# power.net
KiCad netlist of a schematic drawn in Altium Designer
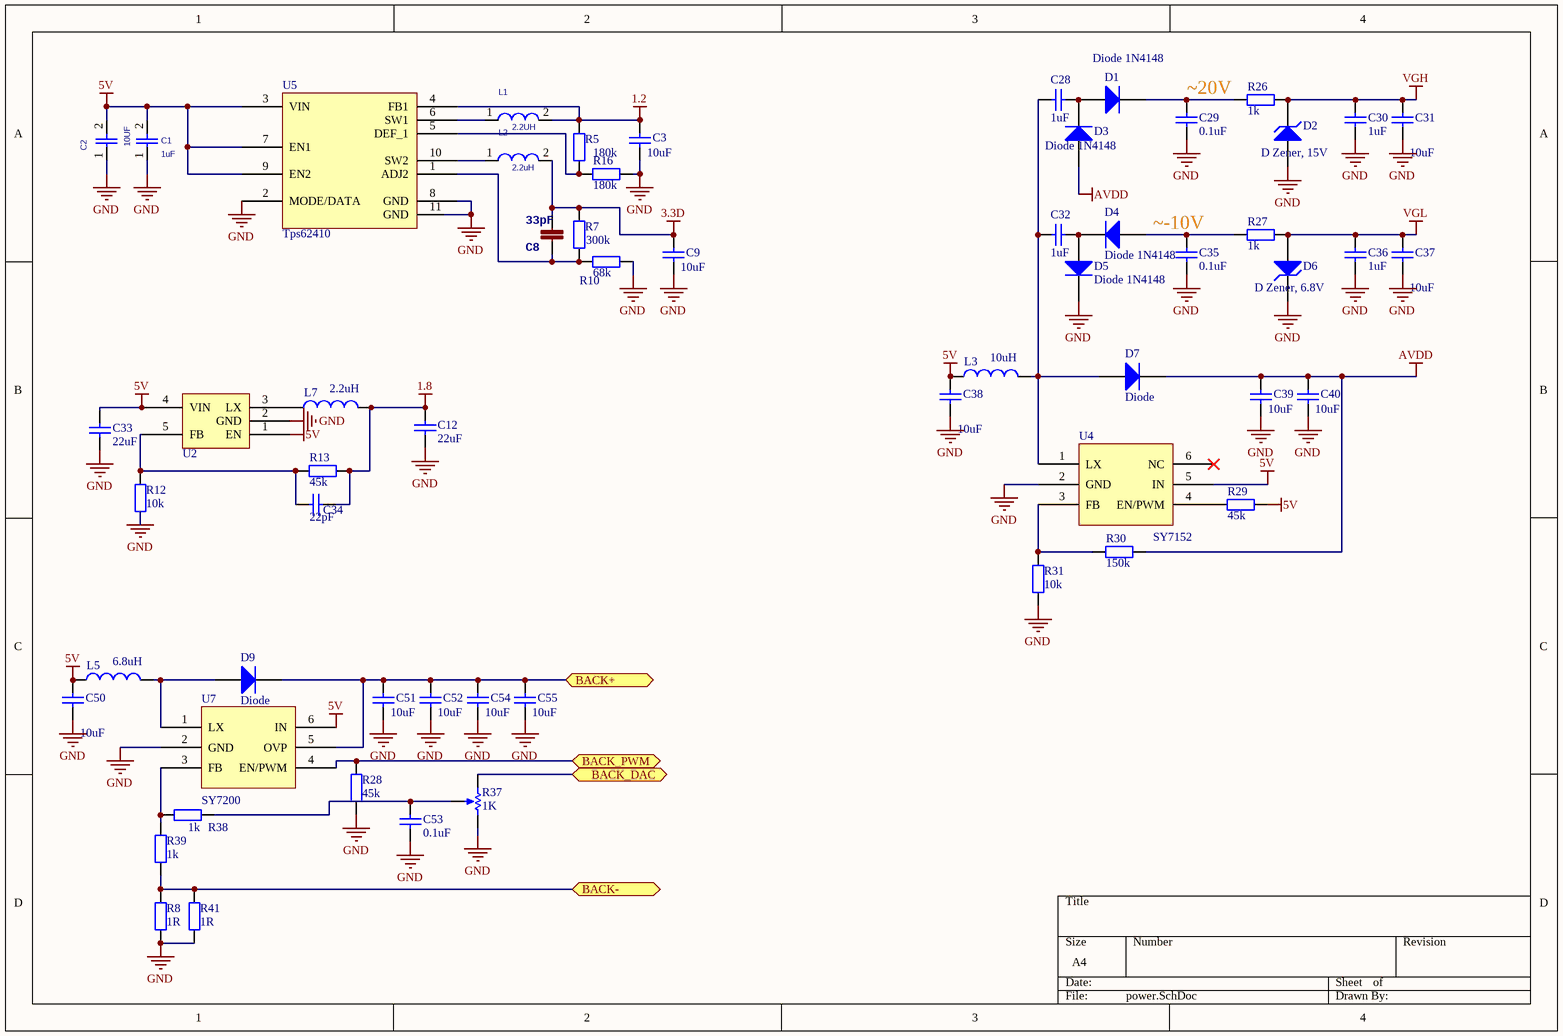
[diagram p0: power.SchDoc]

(export (version "E")
  (design (tool "Eeschema 10.0.6"))
  (components
    (comp (ref "C1") (value "1uF") (footprint "0603") (libsource (lib "*") (part "CAP/0402")))
    (comp (ref "C2") (value "10UF") (footprint "0805") (libsource (lib "*") (part "CAP/0402")))
    (comp (ref "C3")
      (value "10uF")
      (footprint "0805")
      (description "Capacitor")
      (fields (field (name "PUBLISHER") "Altium Limited"))
      (libsource (lib "RTC6705") (part "Cap"))
    )
    (comp (ref "C8")
      (value "33pF")
      (footprint "0402")
      (description "<b>Capacitor</b>\nStandard 0603 ceramic capacitor, and 0.1\" leaded capacitor.")
      (fields (field (name "PARTNO") "CC0402ZRY5V7BB104"))
      (libsource (lib "*") (part "CAP0402-CAP"))
    )
    (comp (ref "C9")
      (value "10uF")
      (footprint "0805")
      (description "Capacitor")
      (fields (field (name "PUBLISHER") "Altium Limited"))
      (libsource (lib "RTC6705") (part "Cap"))
    )
    (comp (ref "C12")
      (value "22uF")
      (footprint "0805")
      (description "Capacitor")
      (fields (field (name "Comment") "Cap") (field (name "PUBLISHER") "Altium Limited"))
      (libsource (lib "RTC6705") (part "Cap"))
    )
    (comp (ref "C28")
      (value "1uF")
      (footprint "0603")
      (description "Capacitor")
      (fields (field (name "PUBLISHER") "Altium Limited"))
      (libsource (lib "RTC6705") (part "Cap"))
    )
    (comp (ref "C29")
      (value "0.1uF")
      (footprint "0603")
      (description "Capacitor")
      (fields (field (name "PUBLISHER") "Altium Limited"))
      (libsource (lib "RTC6705") (part "Cap"))
    )
    (comp (ref "C30")
      (value "1uF")
      (footprint "0603")
      (description "Capacitor")
      (fields (field (name "PUBLISHER") "Altium Limited"))
      (libsource (lib "RTC6705") (part "Cap"))
    )
    (comp (ref "C31")
      (value "10uF")
      (footprint "0805")
      (description "Capacitor")
      (fields (field (name "PUBLISHER") "Altium Limited"))
      (libsource (lib "RTC6705") (part "Cap"))
    )
    (comp (ref "C32")
      (value "1uF")
      (footprint "0603")
      (description "Capacitor")
      (fields (field (name "PUBLISHER") "Altium Limited"))
      (libsource (lib "RTC6705") (part "Cap"))
    )
    (comp (ref "C33")
      (value "22uF")
      (footprint "0805")
      (description "Capacitor")
      (fields (field (name "Comment") "Cap") (field (name "PUBLISHER") "Altium Limited"))
      (libsource (lib "RTC6705") (part "Cap"))
    )
    (comp (ref "C34")
      (value "22pF")
      (footprint "0402")
      (description "Capacitor")
      (fields (field (name "PUBLISHER") "Altium Limited"))
      (libsource (lib "RTC6705") (part "Cap"))
    )
    (comp (ref "C35")
      (value "0.1uF")
      (footprint "0603")
      (description "Capacitor")
      (fields (field (name "PUBLISHER") "Altium Limited"))
      (libsource (lib "RTC6705") (part "Cap"))
    )
    (comp (ref "C36")
      (value "1uF")
      (footprint "0603")
      (description "Capacitor")
      (fields (field (name "PUBLISHER") "Altium Limited"))
      (libsource (lib "RTC6705") (part "Cap"))
    )
    (comp (ref "C37")
      (value "10uF")
      (footprint "0805")
      (description "Capacitor")
      (fields (field (name "PUBLISHER") "Altium Limited"))
      (libsource (lib "RTC6705") (part "Cap"))
    )
    (comp (ref "C38")
      (value "10uF")
      (footprint "0805")
      (description "Capacitor")
      (fields (field (name "PUBLISHER") "Altium Limited"))
      (libsource (lib "RTC6705") (part "Cap"))
    )
    (comp (ref "C39")
      (value "10uF")
      (footprint "0805")
      (description "Capacitor")
      (fields (field (name "PUBLISHER") "Altium Limited"))
      (libsource (lib "RTC6705") (part "Cap"))
    )
    (comp (ref "C40")
      (value "10uF")
      (footprint "0805")
      (description "Capacitor")
      (fields (field (name "PUBLISHER") "Altium Limited"))
      (libsource (lib "RTC6705") (part "Cap"))
    )
    (comp (ref "C50")
      (value "10uF")
      (footprint "0805")
      (description "Capacitor")
      (fields (field (name "PUBLISHER") "Altium Limited"))
      (libsource (lib "RTC6705") (part "Cap"))
    )
    (comp (ref "C51")
      (value "10uF")
      (footprint "0805")
      (description "Capacitor")
      (fields (field (name "PUBLISHER") "Altium Limited"))
      (libsource (lib "RTC6705") (part "Cap"))
    )
    (comp (ref "C52")
      (value "10uF")
      (footprint "0805")
      (description "Capacitor")
      (fields (field (name "PUBLISHER") "Altium Limited"))
      (libsource (lib "RTC6705") (part "Cap"))
    )
    (comp (ref "C53")
      (value "0.1uF")
      (footprint "0402")
      (description "Capacitor")
      (fields (field (name "PUBLISHER") "Altium Limited"))
      (libsource (lib "RTC6705") (part "Cap"))
    )
    (comp (ref "C54")
      (value "10uF")
      (footprint "0603")
      (description "Capacitor")
      (fields (field (name "PUBLISHER") "Altium Limited"))
      (libsource (lib "RTC6705") (part "Cap"))
    )
    (comp (ref "C55")
      (value "10uF")
      (footprint "0603")
      (description "Capacitor")
      (fields (field (name "PUBLISHER") "Altium Limited"))
      (libsource (lib "RTC6705") (part "Cap"))
    )
    (comp (ref "D1")
      (value "Diode 1N4148")
      (footprint "LC-SOD-323")
      (description "High Conductance Fast Diode")
      (fields (field (name "PUBLISHER") "Altium Limited"))
      (libsource (lib "Miscellaneous Devices") (part "Diode 1N4148"))
    )
    (comp (ref "D2")
      (value "D Zener, 15V")
      (footprint "LC-SOD-323")
      (description "Zener Diode")
      (fields (field (name "PUBLISHER") "Altium Limited"))
      (libsource (lib "Miscellaneous Devices") (part "D Zener"))
    )
    (comp (ref "D3")
      (value "Diode 1N4148")
      (footprint "LC-SOD-323")
      (description "High Conductance Fast Diode")
      (fields (field (name "PUBLISHER") "Altium Limited"))
      (libsource (lib "Miscellaneous Devices") (part "Diode 1N4148"))
    )
    (comp (ref "D4")
      (value "Diode 1N4148")
      (footprint "LC-SOD-323")
      (description "High Conductance Fast Diode")
      (fields (field (name "PUBLISHER") "Altium Limited"))
      (libsource (lib "Miscellaneous Devices") (part "Diode 1N4148"))
    )
    (comp (ref "D5")
      (value "Diode 1N4148")
      (footprint "LC-SOD-323")
      (description "High Conductance Fast Diode")
      (fields (field (name "PUBLISHER") "Altium Limited"))
      (libsource (lib "Miscellaneous Devices") (part "Diode 1N4148"))
    )
    (comp (ref "D6")
      (value "D Zener, 6.8V")
      (footprint "LC-SOD-323")
      (description "Zener Diode")
      (fields (field (name "PUBLISHER") "Altium Limited"))
      (libsource (lib "Miscellaneous Devices") (part "D Zener"))
    )
    (comp (ref "D7")
      (value "Diode")
      (footprint "LC-SOD-323")
      (description "Default Diode")
      (fields (field (name "PUBLISHER") "Altium Limited"))
      (libsource (lib "Miscellaneous Devices") (part "Diode"))
    )
    (comp (ref "D9")
      (value "Diode")
      (footprint "SMA")
      (description "Default Diode")
      (fields (field (name "PUBLISHER") "Altium Limited"))
      (libsource (lib "Miscellaneous Devices") (part "Diode"))
    )
    (comp (ref "L1") (value "2.2UH") (footprint "0806") (libsource (lib "*") (part "L/2.5*2.0")))
    (comp (ref "L2") (value "2.2uH") (footprint "0806") (libsource (lib "*") (part "L/2.5*2.0")))
    (comp (ref "L3")
      (value "10uH")
      (footprint "0806")
      (description "Inductor")
      (fields (field (name "PUBLISHER") "Altium Limited"))
      (libsource (lib "Miscellaneous Devices") (part "Inductor"))
    )
    (comp (ref "L5")
      (value "6.8uH")
      (footprint "L4015")
      (description "Inductor")
      (fields (field (name "PUBLISHER") "Altium Limited"))
      (libsource (lib "Miscellaneous Devices") (part "Inductor"))
    )
    (comp (ref "L7")
      (value "2.2uH")
      (footprint "0806")
      (description "Inductor")
      (fields (field (name "PUBLISHER") "Altium Limited"))
      (libsource (lib "Miscellaneous Devices") (part "Inductor"))
    )
    (comp (ref "R5")
      (value "180k")
      (footprint "0402")
      (description "Resistor")
      (fields (field (name "PUBLISHER") "Altium Limited"))
      (libsource (lib "") (part "Res2_2"))
    )
    (comp (ref "R7")
      (value "300k")
      (footprint "0402")
      (description "Resistor")
      (fields (field (name "PUBLISHER") "Altium Limited"))
      (libsource (lib "") (part "Res2_2"))
    )
    (comp (ref "R8")
      (value "1R")
      (footprint "0805")
      (description "Resistor")
      (fields (field (name "PUBLISHER") "Altium Limited"))
      (libsource (lib "RTC6705") (part "Res2"))
    )
    (comp (ref "R10")
      (value "68k")
      (footprint "0402")
      (description "Resistor")
      (fields (field (name "PUBLISHER") "Altium Limited"))
      (libsource (lib "") (part "Res2_1"))
    )
    (comp (ref "R12")
      (value "10k")
      (footprint "0402")
      (description "Resistor")
      (fields (field (name "PUBLISHER") "Altium Limited"))
      (libsource (lib "RTC6705") (part "Res2"))
    )
    (comp (ref "R13")
      (value "45k")
      (footprint "0402")
      (description "Resistor")
      (fields (field (name "PUBLISHER") "Altium Limited"))
      (libsource (lib "") (part "Res2_1"))
    )
    (comp (ref "R16")
      (value "180k")
      (footprint "0402")
      (description "Resistor")
      (fields (field (name "PUBLISHER") "Altium Limited"))
      (libsource (lib "") (part "Res2_1"))
    )
    (comp (ref "R26")
      (value "1k")
      (footprint "0402")
      (description "Resistor")
      (fields (field (name "PUBLISHER") "Altium Limited"))
      (libsource (lib "") (part "Res2_1"))
    )
    (comp (ref "R27")
      (value "1k")
      (footprint "0402")
      (description "Resistor")
      (fields (field (name "PUBLISHER") "Altium Limited"))
      (libsource (lib "") (part "Res2_1"))
    )
    (comp (ref "R28")
      (value "45k")
      (footprint "0402")
      (description "Resistor")
      (fields (field (name "PUBLISHER") "Altium Limited"))
      (libsource (lib "RTC6705") (part "Res2"))
    )
    (comp (ref "R29")
      (value "45k")
      (footprint "0402")
      (description "Resistor")
      (fields (field (name "PUBLISHER") "Altium Limited"))
      (libsource (lib "") (part "Res2_1"))
    )
    (comp (ref "R30")
      (value "150k")
      (footprint "0402")
      (description "Resistor")
      (fields (field (name "PUBLISHER") "Altium Limited"))
      (libsource (lib "") (part "Res2_1"))
    )
    (comp (ref "R31")
      (value "10k")
      (footprint "0402")
      (description "Resistor")
      (fields (field (name "PUBLISHER") "Altium Limited"))
      (libsource (lib "RTC6705") (part "Res2"))
    )
    (comp (ref "R37")
      (value "1K")
      (footprint "POT1")
      (description "Potentiometer")
      (fields (field (name "Comment") "RPot") (field (name "PUBLISHER") "Altium Limited"))
      (libsource (lib "Miscellaneous Devices") (part "RPot"))
    )
    (comp (ref "R38")
      (value "1k")
      (footprint "0402")
      (description "Resistor")
      (fields (field (name "PUBLISHER") "Altium Limited"))
      (libsource (lib "") (part "Res2_3"))
    )
    (comp (ref "R39")
      (value "1k")
      (footprint "0402")
      (description "Resistor")
      (fields (field (name "PUBLISHER") "Altium Limited"))
      (libsource (lib "RTC6705") (part "Res2"))
    )
    (comp (ref "R41")
      (value "1R")
      (footprint "0805")
      (description "Resistor")
      (fields (field (name "PUBLISHER") "Altium Limited"))
      (libsource (lib "RTC6705") (part "Res2"))
    )
    (comp (ref "U2") (value "RT8059") (footprint "SOT23-5") (libsource (lib "WifiGain") (part "RT8059")))
    (comp (ref "U4") (value "SY7152") (footprint "SOT23-6") (libsource (lib "sch") (part "SY7152")))
    (comp (ref "U5") (value "Tps62410") (footprint "DFN-10P-3X3") (libsource (lib "Euler") (part "Tps62410")))
    (comp (ref "U7") (value "SY7200") (footprint "SOT23-6") (libsource (lib "sch") (part "SY7200")))
  )
  (nets
    (net (code "1") (name "/BACK+") (class "Default")
      (node (ref "C51") (pin "2") (pinfunction "2_2") (pintype "passive"))
      (node (ref "C52") (pin "2") (pinfunction "2_2") (pintype "passive"))
      (node (ref "C54") (pin "2") (pinfunction "2_2") (pintype "passive"))
      (node (ref "C55") (pin "2") (pinfunction "2_2") (pintype "passive"))
      (node (ref "D9") (pin "2") (pinfunction "K_2") (pintype "passive"))
      (node (ref "U7") (pin "5") (pinfunction "OVP_5") (pintype "passive"))
    )
    (net (code "2") (name "/BACK-") (class "Default")
      (node (ref "R39") (pin "1") (pinfunction "1_1") (pintype "passive"))
      (node (ref "R41") (pin "2") (pinfunction "2_2") (pintype "passive"))
      (node (ref "R8") (pin "2") (pinfunction "2_2") (pintype "passive"))
    )
    (net (code "3") (name "/BACK_DAC") (class "Default")
      (node (ref "R37") (pin "1") (pinfunction "TOP_1") (pintype "passive"))
    )
    (net (code "4") (name "/BACK_PWM") (class "Default")
      (node (ref "R28") (pin "2") (pinfunction "2_2") (pintype "passive"))
      (node (ref "U7") (pin "4") (pinfunction "EN/PWM_4") (pintype "passive"))
    )
    (net (code "5") (name "1.2") (class "Default")
      (node (ref "C3") (pin "2") (pinfunction "2_2") (pintype "passive"))
      (node (ref "L1") (pin "2") (pinfunction "2_2") (pintype "passive"))
      (node (ref "R5") (pin "1") (pinfunction "1_1") (pintype "passive"))
      (node (ref "U5") (pin "4") (pinfunction "FB1_4") (pintype "passive"))
    )
    (net (code "6") (name "1.8") (class "Default")
      (node (ref "C12") (pin "2") (pinfunction "2_2") (pintype "passive"))
      (node (ref "C34") (pin "1") (pinfunction "1_1") (pintype "passive"))
      (node (ref "L7") (pin "2") (pinfunction "2_2") (pintype "passive"))
      (node (ref "R13") (pin "2") (pinfunction "2_2") (pintype "passive"))
    )
    (net (code "7") (name "3.3D") (class "Default")
      (node (ref "C8") (pin "1") (pinfunction "1_1") (pintype "passive"))
      (node (ref "C9") (pin "2") (pinfunction "2_2") (pintype "passive"))
      (node (ref "L2") (pin "2") (pinfunction "2_2") (pintype "passive"))
      (node (ref "R7") (pin "1") (pinfunction "1_1") (pintype "passive"))
    )
    (net (code "8") (name "5V") (class "Default")
      (node (ref "C1") (pin "2") (pinfunction "2_2") (pintype "passive"))
      (node (ref "C2") (pin "2") (pinfunction "2_2") (pintype "passive"))
      (node (ref "C33") (pin "2") (pinfunction "2_2") (pintype "passive"))
      (node (ref "C38") (pin "2") (pinfunction "2_2") (pintype "passive"))
      (node (ref "C50") (pin "2") (pinfunction "2_2") (pintype "passive"))
      (node (ref "L3") (pin "1") (pinfunction "1_1") (pintype "passive"))
      (node (ref "L5") (pin "1") (pinfunction "1_1") (pintype "passive"))
      (node (ref "R29") (pin "2") (pinfunction "2_2") (pintype "passive"))
      (node (ref "U2") (pin "1") (pinfunction "EN_1") (pintype "passive"))
      (node (ref "U2") (pin "4") (pinfunction "VIN_4") (pintype "passive"))
      (node (ref "U4") (pin "5") (pinfunction "IN_5") (pintype "passive"))
      (node (ref "U5") (pin "3") (pinfunction "VIN_3") (pintype "passive"))
      (node (ref "U5") (pin "7") (pinfunction "EN1_7") (pintype "passive"))
      (node (ref "U5") (pin "9") (pinfunction "EN2_9") (pintype "passive"))
      (node (ref "U7") (pin "6") (pinfunction "IN_6") (pintype "passive"))
    )
    (net (code "9") (name "AVDD") (class "Default")
      (node (ref "C39") (pin "2") (pinfunction "2_2") (pintype "passive"))
      (node (ref "C40") (pin "2") (pinfunction "2_2") (pintype "passive"))
      (node (ref "D3") (pin "1") (pinfunction "A_1") (pintype "passive"))
      (node (ref "D7") (pin "2") (pinfunction "K_2") (pintype "passive"))
      (node (ref "R30") (pin "2") (pinfunction "2_2") (pintype "passive"))
    )
    (net (code "10") (name "GND") (class "Default")
      (node (ref "C1") (pin "1") (pinfunction "1_1") (pintype "passive"))
      (node (ref "C12") (pin "1") (pinfunction "1_1") (pintype "passive"))
      (node (ref "C2") (pin "1") (pinfunction "1_1") (pintype "passive"))
      (node (ref "C29") (pin "2") (pinfunction "2_2") (pintype "passive"))
      (node (ref "C3") (pin "1") (pinfunction "1_1") (pintype "passive"))
      (node (ref "C30") (pin "2") (pinfunction "2_2") (pintype "passive"))
      (node (ref "C31") (pin "1") (pinfunction "1_1") (pintype "passive"))
      (node (ref "C33") (pin "1") (pinfunction "1_1") (pintype "passive"))
      (node (ref "C35") (pin "2") (pinfunction "2_2") (pintype "passive"))
      (node (ref "C36") (pin "2") (pinfunction "2_2") (pintype "passive"))
      (node (ref "C37") (pin "1") (pinfunction "1_1") (pintype "passive"))
      (node (ref "C38") (pin "1") (pinfunction "1_1") (pintype "passive"))
      (node (ref "C39") (pin "1") (pinfunction "1_1") (pintype "passive"))
      (node (ref "C40") (pin "1") (pinfunction "1_1") (pintype "passive"))
      (node (ref "C50") (pin "1") (pinfunction "1_1") (pintype "passive"))
      (node (ref "C51") (pin "1") (pinfunction "1_1") (pintype "passive"))
      (node (ref "C52") (pin "1") (pinfunction "1_1") (pintype "passive"))
      (node (ref "C53") (pin "2") (pinfunction "2_2") (pintype "passive"))
      (node (ref "C54") (pin "1") (pinfunction "1_1") (pintype "passive"))
      (node (ref "C55") (pin "1") (pinfunction "1_1") (pintype "passive"))
      (node (ref "C9") (pin "1") (pinfunction "1_1") (pintype "passive"))
      (node (ref "D2") (pin "1") (pinfunction "A_1") (pintype "passive"))
      (node (ref "D5") (pin "2") (pinfunction "K_2") (pintype "passive"))
      (node (ref "D6") (pin "2") (pinfunction "K_2") (pintype "passive"))
      (node (ref "R10") (pin "2") (pinfunction "2_2") (pintype "passive"))
      (node (ref "R12") (pin "1") (pinfunction "1_1") (pintype "passive"))
      (node (ref "R16") (pin "2") (pinfunction "2_2") (pintype "passive"))
      (node (ref "R28") (pin "1") (pinfunction "1_1") (pintype "passive"))
      (node (ref "R31") (pin "1") (pinfunction "1_1") (pintype "passive"))
      (node (ref "R37") (pin "2") (pinfunction "BOT_2") (pintype "passive"))
      (node (ref "R41") (pin "1") (pinfunction "1_1") (pintype "passive"))
      (node (ref "R8") (pin "1") (pinfunction "1_1") (pintype "passive"))
      (node (ref "U2") (pin "2") (pinfunction "GND_2") (pintype "passive"))
      (node (ref "U4") (pin "2") (pinfunction "GND_2") (pintype "passive"))
      (node (ref "U5") (pin "11") (pinfunction "GND_11") (pintype "passive"))
      (node (ref "U5") (pin "2") (pinfunction "MODE/DATA_2") (pintype "passive"))
      (node (ref "U5") (pin "8") (pinfunction "GND_8") (pintype "passive"))
      (node (ref "U7") (pin "2") (pinfunction "GND_2") (pintype "passive"))
    )
    (net (code "11") (name "Net-(D1-A)") (class "Default")
      (node (ref "C28") (pin "1") (pinfunction "1_1") (pintype "passive"))
      (node (ref "D1") (pin "1") (pinfunction "A_1") (pintype "passive"))
      (node (ref "D3") (pin "2") (pinfunction "K_2") (pintype "passive"))
    )
    (net (code "12") (name "Net-(D1-K)") (class "Default")
      (node (ref "C29") (pin "1") (pinfunction "1_1") (pintype "passive"))
      (node (ref "D1") (pin "2") (pinfunction "K_2") (pintype "passive"))
      (node (ref "R26") (pin "1") (pinfunction "1_1") (pintype "passive"))
    )
    (net (code "13") (name "Net-(D4-A)") (class "Default")
      (node (ref "C35") (pin "1") (pinfunction "1_1") (pintype "passive"))
      (node (ref "D4") (pin "1") (pinfunction "A_1") (pintype "passive"))
      (node (ref "R27") (pin "1") (pinfunction "1_1") (pintype "passive"))
    )
    (net (code "14") (name "Net-(D4-K)") (class "Default")
      (node (ref "C32") (pin "1") (pinfunction "1_1") (pintype "passive"))
      (node (ref "D4") (pin "2") (pinfunction "K_2") (pintype "passive"))
      (node (ref "D5") (pin "1") (pinfunction "A_1") (pintype "passive"))
    )
    (net (code "15") (name "Net-(D7-A)") (class "Default")
      (node (ref "C28") (pin "2") (pinfunction "2_2") (pintype "passive"))
      (node (ref "C32") (pin "2") (pinfunction "2_2") (pintype "passive"))
      (node (ref "D7") (pin "1") (pinfunction "A_1") (pintype "passive"))
      (node (ref "L3") (pin "2") (pinfunction "2_2") (pintype "passive"))
      (node (ref "U4") (pin "1") (pinfunction "LX_1") (pintype "passive"))
    )
    (net (code "16") (name "Net-(D9-A)") (class "Default")
      (node (ref "D9") (pin "1") (pinfunction "A_1") (pintype "passive"))
      (node (ref "L5") (pin "2") (pinfunction "2_2") (pintype "passive"))
      (node (ref "U7") (pin "1") (pinfunction "LX_1") (pintype "passive"))
    )
    (net (code "17") (name "Net-(R37-TAP)") (class "Default")
      (node (ref "C53") (pin "1") (pinfunction "1_1") (pintype "passive"))
      (node (ref "R37") (pin "3") (pinfunction "TAP_3") (pintype "passive"))
      (node (ref "R38") (pin "1") (pinfunction "1_1") (pintype "passive"))
    )
    (net (code "18") (name "Net-(U2-FB)") (class "Default")
      (node (ref "C34") (pin "2") (pinfunction "2_2") (pintype "passive"))
      (node (ref "R12") (pin "2") (pinfunction "2_2") (pintype "passive"))
      (node (ref "R13") (pin "1") (pinfunction "1_1") (pintype "passive"))
      (node (ref "U2") (pin "5") (pinfunction "FB_5") (pintype "passive"))
    )
    (net (code "19") (name "Net-(U2-LX)") (class "Default")
      (node (ref "L7") (pin "1") (pinfunction "1_1") (pintype "passive"))
      (node (ref "U2") (pin "3") (pinfunction "LX_3") (pintype "passive"))
    )
    (net (code "20") (name "Net-(U4-EN{slash}PWM)") (class "Default")
      (node (ref "R29") (pin "1") (pinfunction "1_1") (pintype "passive"))
      (node (ref "U4") (pin "4") (pinfunction "EN/PWM_4") (pintype "passive"))
    )
    (net (code "21") (name "Net-(U4-FB)") (class "Default")
      (node (ref "R30") (pin "1") (pinfunction "1_1") (pintype "passive"))
      (node (ref "R31") (pin "2") (pinfunction "2_2") (pintype "passive"))
      (node (ref "U4") (pin "3") (pinfunction "FB_3") (pintype "passive"))
    )
    (net (code "22") (name "Net-(U5-ADJ2)") (class "Default")
      (node (ref "C8") (pin "2") (pinfunction "2_2") (pintype "passive"))
      (node (ref "R10") (pin "1") (pinfunction "1_1") (pintype "passive"))
      (node (ref "R7") (pin "2") (pinfunction "2_2") (pintype "passive"))
      (node (ref "U5") (pin "1") (pinfunction "ADJ2_1") (pintype "passive"))
    )
    (net (code "23") (name "Net-(U5-DEF_1)") (class "Default")
      (node (ref "R16") (pin "1") (pinfunction "1_1") (pintype "passive"))
      (node (ref "R5") (pin "2") (pinfunction "2_2") (pintype "passive"))
      (node (ref "U5") (pin "5") (pinfunction "DEF_1_5") (pintype "passive"))
    )
    (net (code "24") (name "Net-(U5-SW1)") (class "Default")
      (node (ref "L1") (pin "1") (pinfunction "1_1") (pintype "passive"))
      (node (ref "U5") (pin "6") (pinfunction "SW1_6") (pintype "passive"))
    )
    (net (code "25") (name "Net-(U5-SW2)") (class "Default")
      (node (ref "L2") (pin "1") (pinfunction "1_1") (pintype "passive"))
      (node (ref "U5") (pin "10") (pinfunction "SW2_10") (pintype "passive"))
    )
    (net (code "26") (name "Net-(U7-FB)") (class "Default")
      (node (ref "R38") (pin "2") (pinfunction "2_2") (pintype "passive"))
      (node (ref "R39") (pin "2") (pinfunction "2_2") (pintype "passive"))
      (node (ref "U7") (pin "3") (pinfunction "FB_3") (pintype "passive"))
    )
    (net (code "27") (name "VGH") (class "Default")
      (node (ref "C30") (pin "1") (pinfunction "1_1") (pintype "passive"))
      (node (ref "C31") (pin "2") (pinfunction "2_2") (pintype "passive"))
      (node (ref "D2") (pin "2") (pinfunction "K_2") (pintype "passive"))
      (node (ref "R26") (pin "2") (pinfunction "2_2") (pintype "passive"))
    )
    (net (code "28") (name "VGL") (class "Default")
      (node (ref "C36") (pin "1") (pinfunction "1_1") (pintype "passive"))
      (node (ref "C37") (pin "2") (pinfunction "2_2") (pintype "passive"))
      (node (ref "D6") (pin "1") (pinfunction "A_1") (pintype "passive"))
      (node (ref "R27") (pin "2") (pinfunction "2_2") (pintype "passive"))
    )
    (net (code "29") (name "unconnected-(U4-NC-Pad6)") (class "Default")
      (node (ref "U4") (pin "6") (pinfunction "NC_6") (pintype "passive+no_connect"))
    )
  )
)
